# 7_MBUS.net
KiCad netlist of a schematic drawn in EAGLE
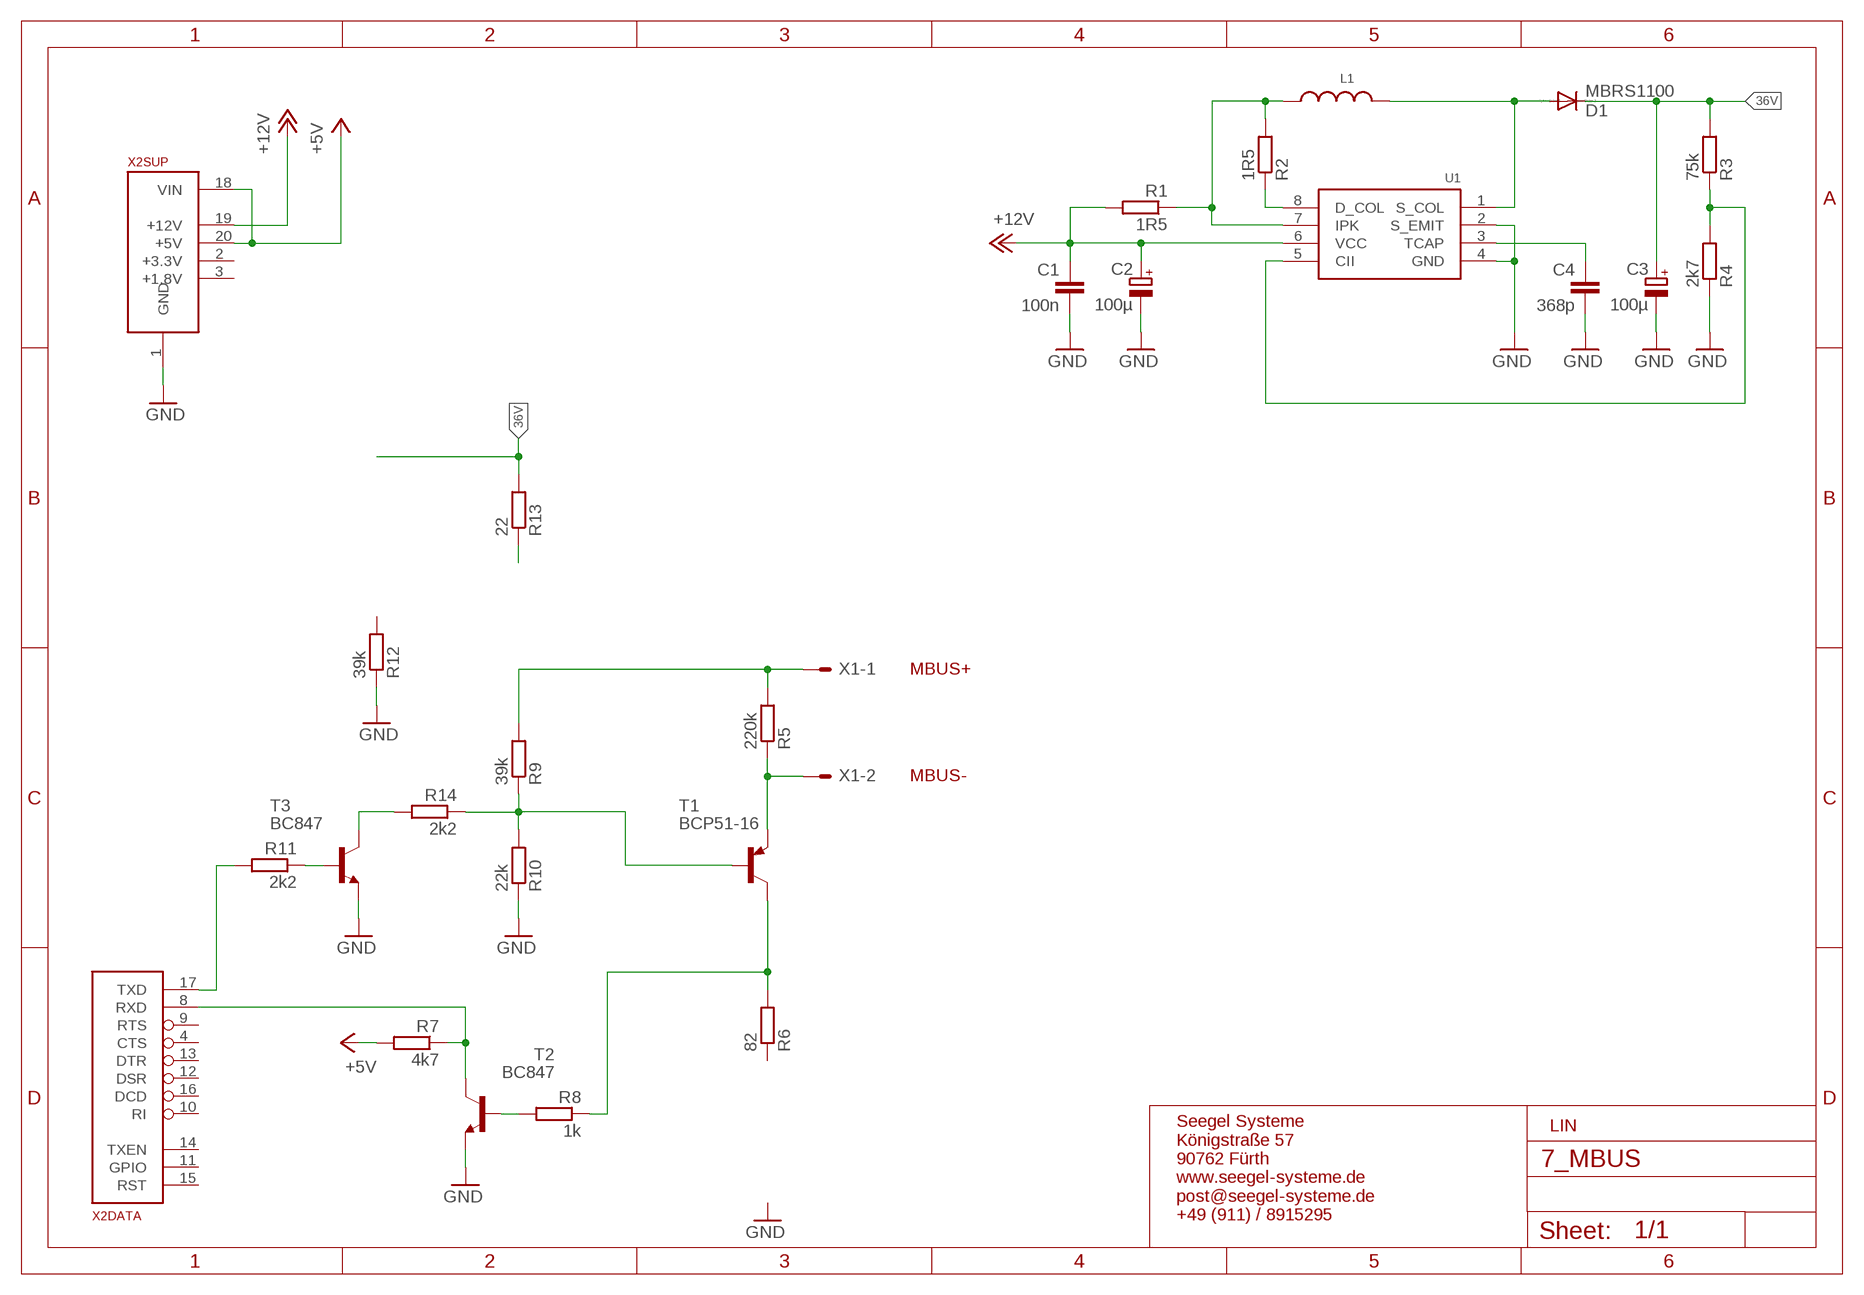
[diagram p0: schematic, sheet 1]

(export (version "E")
  (design (tool "Eeschema 10.0.6"))
  (components
    (comp (ref "C1")
      (value "100n")
      (footprint "eagle-import:C0805")
      (libsource (lib "eagle-import") (part "C-EUC0805"))
    )
    (comp (ref "C2")
      (value "100µ")
      (footprint "eagle-import:PANASONIC_D")
      (libsource (lib "eagle-import") (part "CPOL-EUD"))
    )
    (comp (ref "C3")
      (value "100µ")
      (footprint "eagle-import:PANASONIC_D")
      (libsource (lib "eagle-import") (part "CPOL-EUD"))
    )
    (comp (ref "C4")
      (value "368p")
      (footprint "eagle-import:C0805")
      (libsource (lib "eagle-import") (part "C-EUC0805"))
    )
    (comp (ref "D1")
      (value "MBRS1100")
      (footprint "eagle-import:DO214AA")
      (libsource (lib "eagle-import") (part "DIODE-DO214AA"))
    )
    (comp (ref "L1")
      (value "WE-PD_1260_74477126")
      (footprint "eagle-import:WE-PD_1260_1245_1280_1210")
      (libsource (lib "eagle-import") (part "WE-PD_1260_74477126"))
    )
    (comp (ref "R1")
      (value "1R5")
      (footprint "eagle-import:R0805")
      (libsource (lib "eagle-import") (part "R-EU_R0805"))
    )
    (comp (ref "R2")
      (value "1R5")
      (footprint "eagle-import:R0805")
      (libsource (lib "eagle-import") (part "R-EU_R0805"))
    )
    (comp (ref "R3")
      (value "75k")
      (footprint "eagle-import:R0805")
      (libsource (lib "eagle-import") (part "R-EU_R0805"))
    )
    (comp (ref "R4")
      (value "2k7")
      (footprint "eagle-import:R0805")
      (libsource (lib "eagle-import") (part "R-EU_R0805"))
    )
    (comp (ref "R5")
      (value "220k")
      (footprint "eagle-import:R0805")
      (libsource (lib "eagle-import") (part "R-EU_R0805"))
    )
    (comp (ref "R6")
      (value "82")
      (footprint "eagle-import:R0805")
      (libsource (lib "eagle-import") (part "R-EU_R0805"))
    )
    (comp (ref "R7")
      (value "4k7")
      (footprint "eagle-import:R0805")
      (libsource (lib "eagle-import") (part "R-EU_R0805"))
    )
    (comp (ref "R8")
      (value "1k")
      (footprint "eagle-import:R0805")
      (libsource (lib "eagle-import") (part "R-EU_R0805"))
    )
    (comp (ref "R9")
      (value "39k")
      (footprint "eagle-import:R0805")
      (libsource (lib "eagle-import") (part "R-EU_R0805"))
    )
    (comp (ref "R10")
      (value "22k")
      (footprint "eagle-import:R0805")
      (libsource (lib "eagle-import") (part "R-EU_R0805"))
    )
    (comp (ref "R11")
      (value "2k2")
      (footprint "eagle-import:R0805")
      (libsource (lib "eagle-import") (part "R-EU_R0805"))
    )
    (comp (ref "R12")
      (value "39k")
      (footprint "eagle-import:R0805")
      (libsource (lib "eagle-import") (part "R-EU_R0805"))
    )
    (comp (ref "R13")
      (value "22")
      (footprint "eagle-import:R0805")
      (libsource (lib "eagle-import") (part "R-EU_R0805"))
    )
    (comp (ref "R14")
      (value "2k2")
      (footprint "eagle-import:R0805")
      (libsource (lib "eagle-import") (part "R-EU_R0805"))
    )
    (comp (ref "T1")
      (value "BCP51-16")
      (footprint "eagle-import:SOT223")
      (libsource (lib "eagle-import") (part "-PNP-"))
    )
    (comp (ref "T2")
      (value "BC847")
      (footprint "eagle-import:SOT23")
      (libsource (lib "eagle-import") (part "BC847"))
    )
    (comp (ref "T3")
      (value "BC847")
      (footprint "eagle-import:SOT23")
      (libsource (lib "eagle-import") (part "BC847"))
    )
    (comp (ref "U1")
      (value "MC34063A")
      (footprint "eagle-import:SOIC8_150MIL")
      (libsource (lib "eagle-import") (part "MC34063A"))
    )
    (comp (ref "X1")
      (value "AKL18X-02W")
      (footprint "eagle-import:AKL182-02")
      (libsource (lib "eagle-import") (part "AKL18X-02W"))
    )
    (comp (ref "X2")
      (value "ALLSERIALSLAVE")
      (footprint "eagle-import:DAUGHTER-THT")
      (libsource (lib "eagle-import") (part "ALLSERIALSLAVE"))
    )
  )
  (nets
    (net (code "1") (name "+5V") (class "Default")
      (node (ref "R7") (pin "2") (pinfunction "2_2") (pintype "passive"))
      (node (ref "X2") (pin "18") (pinfunction "VIN_18") (pintype "bidirectional"))
      (node (ref "X2") (pin "20") (pinfunction "+5V_20") (pintype "bidirectional"))
    )
    (net (code "2") (name "+12V") (class "Default")
      (node (ref "C1") (pin "1") (pinfunction "1_1") (pintype "passive"))
      (node (ref "C2") (pin "+") (pinfunction "+_+") (pintype "passive"))
      (node (ref "R1") (pin "2") (pinfunction "2_2") (pintype "passive"))
      (node (ref "U1") (pin "6") (pinfunction "VCC_6") (pintype "bidirectional"))
      (node (ref "X2") (pin "19") (pinfunction "+12V_19") (pintype "bidirectional"))
    )
    (net (code "3") (name "36V") (class "Default")
      (node (ref "C3") (pin "+") (pinfunction "+_+") (pintype "passive"))
      (node (ref "D1") (pin "C") (pinfunction "C_C") (pintype "passive"))
      (node (ref "R13") (pin "2") (pinfunction "2_2") (pintype "passive"))
      (node (ref "R3") (pin "2") (pinfunction "2_2") (pintype "passive"))
    )
    (net (code "4") (name "GND") (class "Default")
      (node (ref "C1") (pin "2") (pinfunction "2_2") (pintype "passive"))
      (node (ref "C2") (pin "-") (pinfunction "-_-") (pintype "passive"))
      (node (ref "C3") (pin "-") (pinfunction "-_-") (pintype "passive"))
      (node (ref "C4") (pin "2") (pinfunction "2_2") (pintype "passive"))
      (node (ref "R10") (pin "1") (pinfunction "1_1") (pintype "passive"))
      (node (ref "R12") (pin "1") (pinfunction "1_1") (pintype "passive"))
      (node (ref "R4") (pin "1") (pinfunction "1_1") (pintype "passive"))
      (node (ref "T2") (pin "2") (pinfunction "E_2") (pintype "passive"))
      (node (ref "T3") (pin "2") (pinfunction "E_2") (pintype "passive"))
      (node (ref "U1") (pin "2") (pinfunction "S_EMIT_2") (pintype "bidirectional"))
      (node (ref "U1") (pin "4") (pinfunction "GND_4") (pintype "bidirectional"))
      (node (ref "X2") (pin "1") (pinfunction "GND_1") (pintype "bidirectional"))
    )
    (net (code "5") (name "Net-(R6-Pad2)") (class "Default")
      (node (ref "R6") (pin "2") (pinfunction "2_2") (pintype "passive"))
      (node (ref "R8") (pin "1") (pinfunction "1_1") (pintype "passive"))
      (node (ref "T1") (pin "2") (pinfunction "C_2") (pintype "passive"))
      (node (ref "T1") (pin "4") (pinfunction "C_4") (pintype "passive"))
    )
    (net (code "6") (name "Net-(T1-B)") (class "Default")
      (node (ref "R10") (pin "2") (pinfunction "2_2") (pintype "passive"))
      (node (ref "R14") (pin "1") (pinfunction "1_1") (pintype "passive"))
      (node (ref "R9") (pin "1") (pinfunction "1_1") (pintype "passive"))
      (node (ref "T1") (pin "1") (pinfunction "B_1") (pintype "passive"))
    )
    (net (code "7") (name "Net-(T1-E)") (class "Default")
      (node (ref "R5") (pin "1") (pinfunction "1_1") (pintype "passive"))
      (node (ref "T1") (pin "3") (pinfunction "E_3") (pintype "passive"))
      (node (ref "X1") (pin "P$2") (pinfunction "S_P$2") (pintype "passive"))
    )
    (net (code "8") (name "Net-(T2-B)") (class "Default")
      (node (ref "R8") (pin "2") (pinfunction "2_2") (pintype "passive"))
      (node (ref "T2") (pin "1") (pinfunction "B_1") (pintype "passive"))
    )
    (net (code "9") (name "Net-(T2-C)") (class "Default")
      (node (ref "R7") (pin "1") (pinfunction "1_1") (pintype "passive"))
      (node (ref "T2") (pin "3") (pinfunction "C_3") (pintype "passive"))
      (node (ref "X2") (pin "8") (pinfunction "RXD_8") (pintype "input"))
    )
    (net (code "10") (name "Net-(T3-B)") (class "Default")
      (node (ref "R11") (pin "1") (pinfunction "1_1") (pintype "passive"))
      (node (ref "T3") (pin "1") (pinfunction "B_1") (pintype "passive"))
    )
    (net (code "11") (name "Net-(T3-C)") (class "Default")
      (node (ref "R14") (pin "2") (pinfunction "2_2") (pintype "passive"))
      (node (ref "T3") (pin "3") (pinfunction "C_3") (pintype "passive"))
    )
    (net (code "12") (name "Net-(U1-CII)") (class "Default")
      (node (ref "R3") (pin "1") (pinfunction "1_1") (pintype "passive"))
      (node (ref "R4") (pin "2") (pinfunction "2_2") (pintype "passive"))
      (node (ref "U1") (pin "5") (pinfunction "CII_5") (pintype "bidirectional"))
    )
    (net (code "13") (name "Net-(U1-D_COL)") (class "Default")
      (node (ref "R2") (pin "1") (pinfunction "1_1") (pintype "passive"))
      (node (ref "U1") (pin "8") (pinfunction "D_COL_8") (pintype "bidirectional"))
    )
    (net (code "14") (name "Net-(U1-IPK)") (class "Default")
      (node (ref "L1") (pin "2") (pinfunction "2_2") (pintype "passive"))
      (node (ref "R1") (pin "1") (pinfunction "1_1") (pintype "passive"))
      (node (ref "R2") (pin "2") (pinfunction "2_2") (pintype "passive"))
      (node (ref "U1") (pin "7") (pinfunction "IPK_7") (pintype "bidirectional"))
    )
    (net (code "15") (name "Net-(U1-S_COL)") (class "Default")
      (node (ref "D1") (pin "A") (pinfunction "A_A") (pintype "passive"))
      (node (ref "L1") (pin "1") (pinfunction "1_1") (pintype "passive"))
      (node (ref "U1") (pin "1") (pinfunction "S_COL_1") (pintype "bidirectional"))
    )
    (net (code "16") (name "Net-(U1-TCAP)") (class "Default")
      (node (ref "C4") (pin "1") (pinfunction "1_1") (pintype "passive"))
      (node (ref "U1") (pin "3") (pinfunction "TCAP_3") (pintype "bidirectional"))
    )
    (net (code "17") (name "Net-(X1A-S)") (class "Default")
      (node (ref "R5") (pin "2") (pinfunction "2_2") (pintype "passive"))
      (node (ref "R9") (pin "2") (pinfunction "2_2") (pintype "passive"))
      (node (ref "X1") (pin "P$1") (pinfunction "S_P$1") (pintype "passive"))
    )
    (net (code "18") (name "Net-(X2A-TXD)") (class "Default")
      (node (ref "R11") (pin "2") (pinfunction "2_2") (pintype "passive"))
      (node (ref "X2") (pin "17") (pinfunction "TXD_17") (pintype "output"))
    )
    (net (code "19") (name "unconnected-(R6-Pad1)") (class "Default")
      (node (ref "R6") (pin "1") (pinfunction "1_1") (pintype "passive"))
    )
    (net (code "20") (name "unconnected-(R12-Pad2)") (class "Default")
      (node (ref "R12") (pin "2") (pinfunction "2_2") (pintype "passive"))
    )
    (net (code "21") (name "unconnected-(R13-Pad1)") (class "Default")
      (node (ref "R13") (pin "1") (pinfunction "1_1") (pintype "passive"))
    )
    (net (code "22") (name "unconnected-(X2A-CTS-Pad4)") (class "Default")
      (node (ref "X2") (pin "4") (pinfunction "CTS_4") (pintype "input"))
    )
    (net (code "23") (name "unconnected-(X2A-DCD-Pad16)") (class "Default")
      (node (ref "X2") (pin "16") (pinfunction "DCD_16") (pintype "input"))
    )
    (net (code "24") (name "unconnected-(X2A-DSR-Pad12)") (class "Default")
      (node (ref "X2") (pin "12") (pinfunction "DSR_12") (pintype "input"))
    )
    (net (code "25") (name "unconnected-(X2A-DTR-Pad13)") (class "Default")
      (node (ref "X2") (pin "13") (pinfunction "DTR_13") (pintype "output"))
    )
    (net (code "26") (name "unconnected-(X2A-GPIO-Pad11)") (class "Default")
      (node (ref "X2") (pin "11") (pinfunction "GPIO_11") (pintype "bidirectional"))
    )
    (net (code "27") (name "unconnected-(X2A-RI-Pad10)") (class "Default")
      (node (ref "X2") (pin "10") (pinfunction "RI_10") (pintype "input"))
    )
    (net (code "28") (name "unconnected-(X2A-RST-Pad15)") (class "Default")
      (node (ref "X2") (pin "15") (pinfunction "RST_15") (pintype "bidirectional"))
    )
    (net (code "29") (name "unconnected-(X2A-RTS-Pad9)") (class "Default")
      (node (ref "X2") (pin "9") (pinfunction "RTS_9") (pintype "output"))
    )
    (net (code "30") (name "unconnected-(X2A-TXEN-Pad14)") (class "Default")
      (node (ref "X2") (pin "14") (pinfunction "TXEN_14") (pintype "output"))
    )
    (net (code "31") (name "unconnected-(X2B-+1.8V-Pad3)") (class "Default")
      (node (ref "X2") (pin "3") (pinfunction "+1.8V_3") (pintype "bidirectional"))
    )
    (net (code "32") (name "unconnected-(X2B-+3.3V-Pad2)") (class "Default")
      (node (ref "X2") (pin "2") (pinfunction "+3.3V_2") (pintype "bidirectional"))
    )
  )
)
